# AMC_Connector.net
KiCad netlist of a schematic drawn in Altium Designer
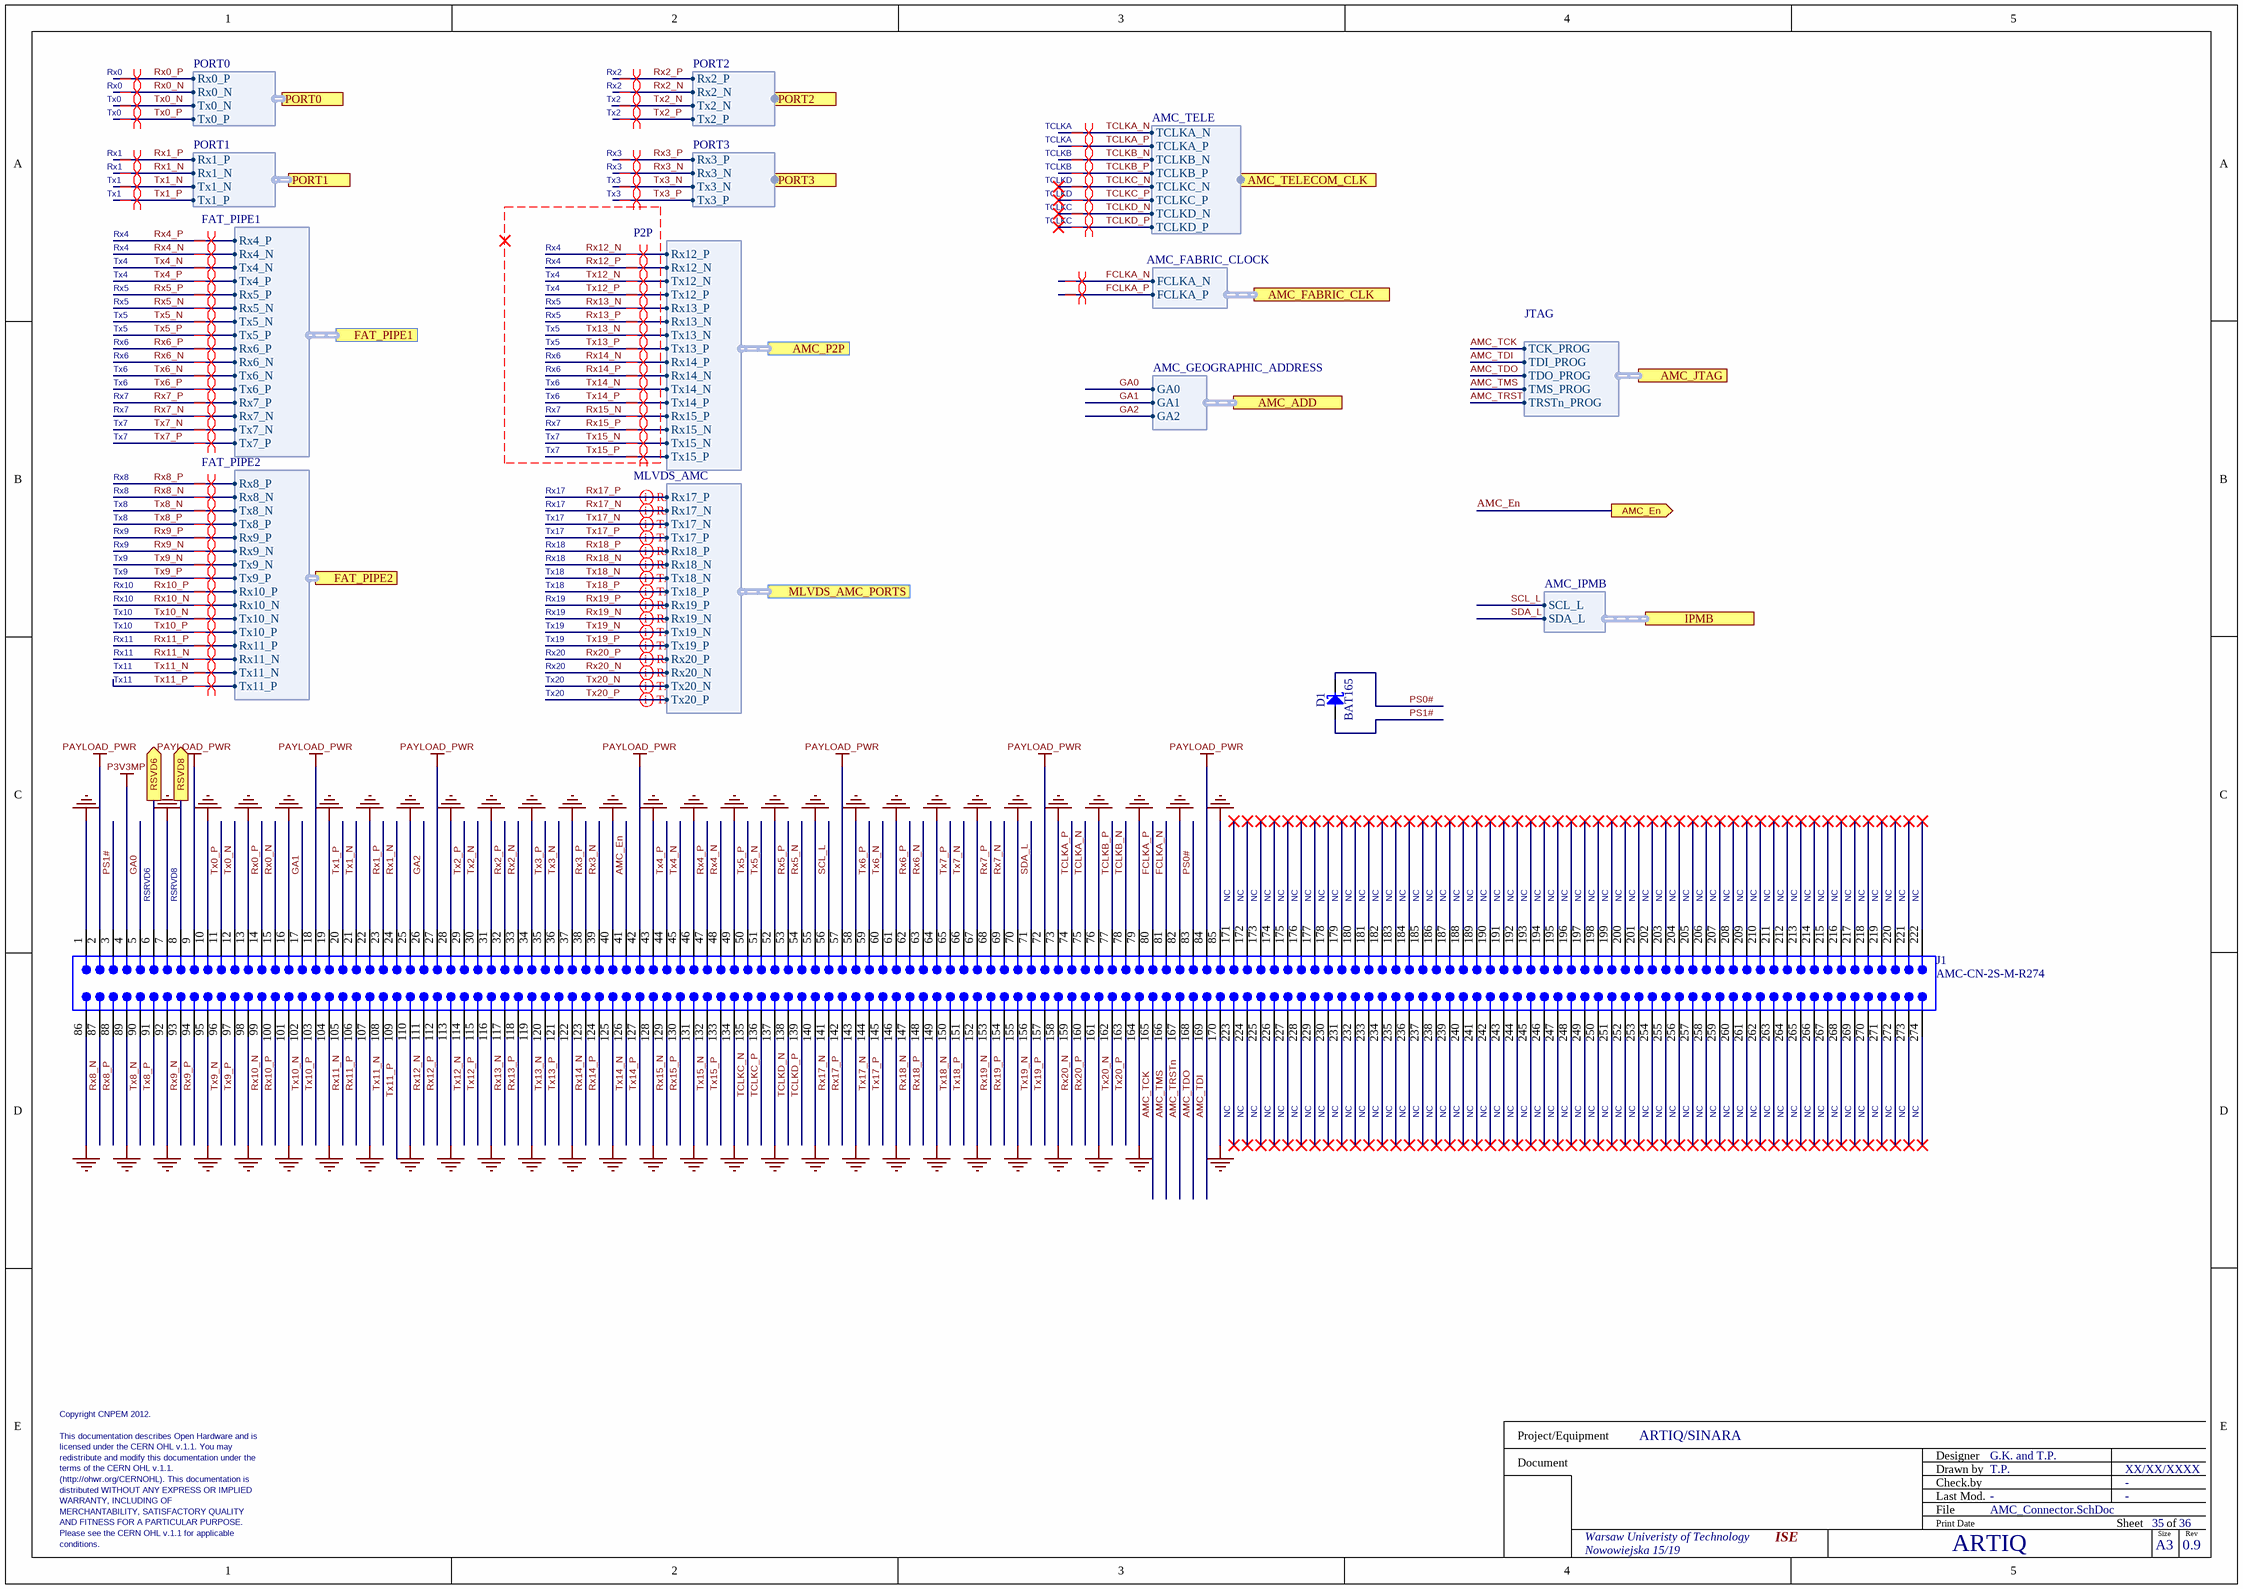
[diagram p0: AMC_Connector.SchDoc]

(export (version "E")
  (design (tool "Eeschema 10.0.6"))
  (components
    (comp (ref "D1")
      (value "BAT165")
      (footprint "SOD2512X110N")
      (description "Schottky Diode")
      (fields
        (field (name "MANUFACTURER") "INFINEON")
        (field (name "VOLTAGE") "40V")
        (field (name "AUTHOR") "CERN DEM JLC")
      )
      (libsource (lib "ICs And Semiconductors") (part "Diode Schottky"))
    )
    (comp (ref "J1")
      (value "AMC-CN-2S-M-R274")
      (footprint "AMC-GF-2D-750-O274")
      (description "Golden finger, AMC, Dual, Opposite, Pitch 0.75mm, 170-Position")
      (fields (field (name "PUBLISHER") "Altium"))
      (libsource (lib "Altium Shanghai") (part "CMP-0001-00058-2"))
    )
  )
  (nets
    (net (code "14") (name "/AMC_En") (class "Default")
      (node (ref "J1") (pin "41") (pinfunction "41_41") (pintype "passive"))
    )
    (net (code "15") (name "/AMC_TCK") (class "Default")
      (node (ref "J1") (pin "165") (pinfunction "165_165") (pintype "passive"))
    )
    (net (code "16") (name "/AMC_TDI") (class "Default")
      (node (ref "J1") (pin "169") (pinfunction "169_169") (pintype "passive"))
    )
    (net (code "17") (name "/AMC_TDO") (class "Default")
      (node (ref "J1") (pin "168") (pinfunction "168_168") (pintype "passive"))
    )
    (net (code "18") (name "/AMC_TMS") (class "Default")
      (node (ref "J1") (pin "166") (pinfunction "166_166") (pintype "passive"))
    )
    (net (code "19") (name "/AMC_TRSTn") (class "Default")
      (node (ref "J1") (pin "167") (pinfunction "167_167") (pintype "passive"))
    )
    (net (code "20") (name "/FCLKA_N") (class "Default")
      (node (ref "J1") (pin "81") (pinfunction "81_81") (pintype "passive"))
    )
    (net (code "21") (name "/FCLKA_P") (class "Default")
      (node (ref "J1") (pin "80") (pinfunction "80_80") (pintype "passive"))
    )
    (net (code "22") (name "/GA0") (class "Default")
      (node (ref "J1") (pin "5") (pinfunction "5_5") (pintype "passive"))
    )
    (net (code "23") (name "/GA1") (class "Default")
      (node (ref "J1") (pin "17") (pinfunction "17_17") (pintype "passive"))
    )
    (net (code "24") (name "/GA2") (class "Default")
      (node (ref "J1") (pin "26") (pinfunction "26_26") (pintype "passive"))
    )
    (net (code "25") (name "/PS0#") (class "Default")
      (node (ref "D1") (pin "1") (pinfunction "C_1") (pintype "passive"))
      (node (ref "J1") (pin "83") (pinfunction "83_83") (pintype "passive"))
    )
    (net (code "26") (name "/PS1#") (class "Default")
      (node (ref "D1") (pin "2") (pinfunction "A_2") (pintype "passive"))
      (node (ref "J1") (pin "3") (pinfunction "3_3") (pintype "passive"))
    )
    (net (code "27") (name "/RSVD6") (class "Default")
      (node (ref "J1") (pin "6") (pinfunction "6_6") (pintype "passive"))
    )
    (net (code "28") (name "/RSVD8") (class "Default")
      (node (ref "J1") (pin "8") (pinfunction "8_8") (pintype "passive"))
    )
    (net (code "29") (name "/Rx0_N") (class "Default")
      (node (ref "J1") (pin "15") (pinfunction "15_15") (pintype "passive"))
    )
    (net (code "30") (name "/Rx0_P") (class "Default")
      (node (ref "J1") (pin "14") (pinfunction "14_14") (pintype "passive"))
    )
    (net (code "31") (name "/Rx1_N") (class "Default")
      (node (ref "J1") (pin "24") (pinfunction "24_24") (pintype "passive"))
    )
    (net (code "32") (name "/Rx1_P") (class "Default")
      (node (ref "J1") (pin "23") (pinfunction "23_23") (pintype "passive"))
    )
    (net (code "33") (name "/Rx2_N") (class "Default")
      (node (ref "J1") (pin "33") (pinfunction "33_33") (pintype "passive"))
    )
    (net (code "34") (name "/Rx2_P") (class "Default")
      (node (ref "J1") (pin "32") (pinfunction "32_32") (pintype "passive"))
    )
    (net (code "35") (name "/Rx3_N") (class "Default")
      (node (ref "J1") (pin "39") (pinfunction "39_39") (pintype "passive"))
    )
    (net (code "36") (name "/Rx3_P") (class "Default")
      (node (ref "J1") (pin "38") (pinfunction "38_38") (pintype "passive"))
    )
    (net (code "37") (name "/Rx4_N") (class "Default")
      (node (ref "J1") (pin "48") (pinfunction "48_48") (pintype "passive"))
    )
    (net (code "38") (name "/Rx4_P") (class "Default")
      (node (ref "J1") (pin "47") (pinfunction "47_47") (pintype "passive"))
    )
    (net (code "39") (name "/Rx5_N") (class "Default")
      (node (ref "J1") (pin "54") (pinfunction "54_54") (pintype "passive"))
    )
    (net (code "40") (name "/Rx5_P") (class "Default")
      (node (ref "J1") (pin "53") (pinfunction "53_53") (pintype "passive"))
    )
    (net (code "41") (name "/Rx6_N") (class "Default")
      (node (ref "J1") (pin "63") (pinfunction "63_63") (pintype "passive"))
    )
    (net (code "42") (name "/Rx6_P") (class "Default")
      (node (ref "J1") (pin "62") (pinfunction "62_62") (pintype "passive"))
    )
    (net (code "43") (name "/Rx7_N") (class "Default")
      (node (ref "J1") (pin "69") (pinfunction "69_69") (pintype "passive"))
    )
    (net (code "44") (name "/Rx7_P") (class "Default")
      (node (ref "J1") (pin "68") (pinfunction "68_68") (pintype "passive"))
    )
    (net (code "45") (name "/Rx8_N") (class "Default")
      (node (ref "J1") (pin "87") (pinfunction "87_87") (pintype "passive"))
    )
    (net (code "46") (name "/Rx8_P") (class "Default")
      (node (ref "J1") (pin "88") (pinfunction "88_88") (pintype "passive"))
    )
    (net (code "47") (name "/Rx9_N") (class "Default")
      (node (ref "J1") (pin "93") (pinfunction "93_93") (pintype "passive"))
    )
    (net (code "48") (name "/Rx9_P") (class "Default")
      (node (ref "J1") (pin "94") (pinfunction "94_94") (pintype "passive"))
    )
    (net (code "49") (name "/Rx10_N") (class "Default")
      (node (ref "J1") (pin "99") (pinfunction "99_99") (pintype "passive"))
    )
    (net (code "50") (name "/Rx10_P") (class "Default")
      (node (ref "J1") (pin "100") (pinfunction "100_100") (pintype "passive"))
    )
    (net (code "51") (name "/Rx11_N") (class "Default")
      (node (ref "J1") (pin "105") (pinfunction "105_105") (pintype "passive"))
    )
    (net (code "52") (name "/Rx11_P") (class "Default")
      (node (ref "J1") (pin "106") (pinfunction "106_106") (pintype "passive"))
    )
    (net (code "53") (name "/Rx12_N") (class "Default")
      (node (ref "J1") (pin "111") (pinfunction "111_111") (pintype "passive"))
    )
    (net (code "54") (name "/Rx12_P") (class "Default")
      (node (ref "J1") (pin "112") (pinfunction "112_112") (pintype "passive"))
    )
    (net (code "55") (name "/Rx13_N") (class "Default")
      (node (ref "J1") (pin "117") (pinfunction "117_117") (pintype "passive"))
    )
    (net (code "56") (name "/Rx13_P") (class "Default")
      (node (ref "J1") (pin "118") (pinfunction "118_118") (pintype "passive"))
    )
    (net (code "57") (name "/Rx14_N") (class "Default")
      (node (ref "J1") (pin "123") (pinfunction "123_123") (pintype "passive"))
    )
    (net (code "58") (name "/Rx14_P") (class "Default")
      (node (ref "J1") (pin "124") (pinfunction "124_124") (pintype "passive"))
    )
    (net (code "59") (name "/Rx15_N") (class "Default")
      (node (ref "J1") (pin "129") (pinfunction "129_129") (pintype "passive"))
    )
    (net (code "60") (name "/Rx15_P") (class "Default")
      (node (ref "J1") (pin "130") (pinfunction "130_130") (pintype "passive"))
    )
    (net (code "61") (name "/Rx17_N") (class "Default")
      (node (ref "J1") (pin "141") (pinfunction "141_141") (pintype "passive"))
    )
    (net (code "62") (name "/Rx17_P") (class "Default")
      (node (ref "J1") (pin "142") (pinfunction "142_142") (pintype "passive"))
    )
    (net (code "63") (name "/Rx18_N") (class "Default")
      (node (ref "J1") (pin "147") (pinfunction "147_147") (pintype "passive"))
    )
    (net (code "64") (name "/Rx18_P") (class "Default")
      (node (ref "J1") (pin "148") (pinfunction "148_148") (pintype "passive"))
    )
    (net (code "65") (name "/Rx19_N") (class "Default")
      (node (ref "J1") (pin "153") (pinfunction "153_153") (pintype "passive"))
    )
    (net (code "66") (name "/Rx19_P") (class "Default")
      (node (ref "J1") (pin "154") (pinfunction "154_154") (pintype "passive"))
    )
    (net (code "67") (name "/Rx20_N") (class "Default")
      (node (ref "J1") (pin "159") (pinfunction "159_159") (pintype "passive"))
    )
    (net (code "68") (name "/Rx20_P") (class "Default")
      (node (ref "J1") (pin "160") (pinfunction "160_160") (pintype "passive"))
    )
    (net (code "69") (name "/SCL_L") (class "Default")
      (node (ref "J1") (pin "56") (pinfunction "56_56") (pintype "passive"))
    )
    (net (code "70") (name "/SDA_L") (class "Default")
      (node (ref "J1") (pin "71") (pinfunction "71_71") (pintype "passive"))
    )
    (net (code "71") (name "/TCLKA_N") (class "Default")
      (node (ref "J1") (pin "75") (pinfunction "75_75") (pintype "passive"))
    )
    (net (code "72") (name "/TCLKA_P") (class "Default")
      (node (ref "J1") (pin "74") (pinfunction "74_74") (pintype "passive"))
    )
    (net (code "73") (name "/TCLKB_N") (class "Default")
      (node (ref "J1") (pin "78") (pinfunction "78_78") (pintype "passive"))
    )
    (net (code "74") (name "/TCLKB_P") (class "Default")
      (node (ref "J1") (pin "77") (pinfunction "77_77") (pintype "passive"))
    )
    (net (code "75") (name "/TCLKC_N") (class "Default")
      (node (ref "J1") (pin "135") (pinfunction "135_135") (pintype "passive"))
    )
    (net (code "76") (name "/TCLKC_P") (class "Default")
      (node (ref "J1") (pin "136") (pinfunction "136_136") (pintype "passive"))
    )
    (net (code "77") (name "/TCLKD_N") (class "Default")
      (node (ref "J1") (pin "138") (pinfunction "138_138") (pintype "passive"))
    )
    (net (code "78") (name "/TCLKD_P") (class "Default")
      (node (ref "J1") (pin "139") (pinfunction "139_139") (pintype "passive"))
    )
    (net (code "79") (name "/Tx0_N") (class "Default")
      (node (ref "J1") (pin "12") (pinfunction "12_12") (pintype "passive"))
    )
    (net (code "80") (name "/Tx0_P") (class "Default")
      (node (ref "J1") (pin "11") (pinfunction "11_11") (pintype "passive"))
    )
    (net (code "81") (name "/Tx1_N") (class "Default")
      (node (ref "J1") (pin "21") (pinfunction "21_21") (pintype "passive"))
    )
    (net (code "82") (name "/Tx1_P") (class "Default")
      (node (ref "J1") (pin "20") (pinfunction "20_20") (pintype "passive"))
    )
    (net (code "83") (name "/Tx2_N") (class "Default")
      (node (ref "J1") (pin "30") (pinfunction "30_30") (pintype "passive"))
    )
    (net (code "84") (name "/Tx2_P") (class "Default")
      (node (ref "J1") (pin "29") (pinfunction "29_29") (pintype "passive"))
    )
    (net (code "85") (name "/Tx3_N") (class "Default")
      (node (ref "J1") (pin "36") (pinfunction "36_36") (pintype "passive"))
    )
    (net (code "86") (name "/Tx3_P") (class "Default")
      (node (ref "J1") (pin "35") (pinfunction "35_35") (pintype "passive"))
    )
    (net (code "87") (name "/Tx4_N") (class "Default")
      (node (ref "J1") (pin "45") (pinfunction "45_45") (pintype "passive"))
    )
    (net (code "88") (name "/Tx4_P") (class "Default")
      (node (ref "J1") (pin "44") (pinfunction "44_44") (pintype "passive"))
    )
    (net (code "89") (name "/Tx5_N") (class "Default")
      (node (ref "J1") (pin "51") (pinfunction "51_51") (pintype "passive"))
    )
    (net (code "90") (name "/Tx5_P") (class "Default")
      (node (ref "J1") (pin "50") (pinfunction "50_50") (pintype "passive"))
    )
    (net (code "91") (name "/Tx6_N") (class "Default")
      (node (ref "J1") (pin "60") (pinfunction "60_60") (pintype "passive"))
    )
    (net (code "92") (name "/Tx6_P") (class "Default")
      (node (ref "J1") (pin "59") (pinfunction "59_59") (pintype "passive"))
    )
    (net (code "93") (name "/Tx7_N") (class "Default")
      (node (ref "J1") (pin "66") (pinfunction "66_66") (pintype "passive"))
    )
    (net (code "94") (name "/Tx7_P") (class "Default")
      (node (ref "J1") (pin "65") (pinfunction "65_65") (pintype "passive"))
    )
    (net (code "95") (name "/Tx8_N") (class "Default")
      (node (ref "J1") (pin "90") (pinfunction "90_90") (pintype "passive"))
    )
    (net (code "96") (name "/Tx8_P") (class "Default")
      (node (ref "J1") (pin "91") (pinfunction "91_91") (pintype "passive"))
    )
    (net (code "97") (name "/Tx9_N") (class "Default")
      (node (ref "J1") (pin "96") (pinfunction "96_96") (pintype "passive"))
    )
    (net (code "98") (name "/Tx9_P") (class "Default")
      (node (ref "J1") (pin "97") (pinfunction "97_97") (pintype "passive"))
    )
    (net (code "99") (name "/Tx10_N") (class "Default")
      (node (ref "J1") (pin "102") (pinfunction "102_102") (pintype "passive"))
    )
    (net (code "100") (name "/Tx10_P") (class "Default")
      (node (ref "J1") (pin "103") (pinfunction "103_103") (pintype "passive"))
    )
    (net (code "101") (name "/Tx11_N") (class "Default")
      (node (ref "J1") (pin "108") (pinfunction "108_108") (pintype "passive"))
    )
    (net (code "102") (name "/Tx11_P") (class "Default")
      (node (ref "J1") (pin "109") (pinfunction "109_109") (pintype "passive"))
    )
    (net (code "103") (name "/Tx12_N") (class "Default")
      (node (ref "J1") (pin "114") (pinfunction "114_114") (pintype "passive"))
    )
    (net (code "104") (name "/Tx12_P") (class "Default")
      (node (ref "J1") (pin "115") (pinfunction "115_115") (pintype "passive"))
    )
    (net (code "105") (name "/Tx13_N") (class "Default")
      (node (ref "J1") (pin "120") (pinfunction "120_120") (pintype "passive"))
    )
    (net (code "106") (name "/Tx13_P") (class "Default")
      (node (ref "J1") (pin "121") (pinfunction "121_121") (pintype "passive"))
    )
    (net (code "107") (name "/Tx14_N") (class "Default")
      (node (ref "J1") (pin "126") (pinfunction "126_126") (pintype "passive"))
    )
    (net (code "108") (name "/Tx14_P") (class "Default")
      (node (ref "J1") (pin "127") (pinfunction "127_127") (pintype "passive"))
    )
    (net (code "109") (name "/Tx15_N") (class "Default")
      (node (ref "J1") (pin "132") (pinfunction "132_132") (pintype "passive"))
    )
    (net (code "110") (name "/Tx15_P") (class "Default")
      (node (ref "J1") (pin "133") (pinfunction "133_133") (pintype "passive"))
    )
    (net (code "111") (name "/Tx17_N") (class "Default")
      (node (ref "J1") (pin "144") (pinfunction "144_144") (pintype "passive"))
    )
    (net (code "112") (name "/Tx17_P") (class "Default")
      (node (ref "J1") (pin "145") (pinfunction "145_145") (pintype "passive"))
    )
    (net (code "113") (name "/Tx18_N") (class "Default")
      (node (ref "J1") (pin "150") (pinfunction "150_150") (pintype "passive"))
    )
    (net (code "114") (name "/Tx18_P") (class "Default")
      (node (ref "J1") (pin "151") (pinfunction "151_151") (pintype "passive"))
    )
    (net (code "115") (name "/Tx19_N") (class "Default")
      (node (ref "J1") (pin "156") (pinfunction "156_156") (pintype "passive"))
    )
    (net (code "116") (name "/Tx19_P") (class "Default")
      (node (ref "J1") (pin "157") (pinfunction "157_157") (pintype "passive"))
    )
    (net (code "117") (name "/Tx20_N") (class "Default")
      (node (ref "J1") (pin "162") (pinfunction "162_162") (pintype "passive"))
    )
    (net (code "118") (name "/Tx20_P") (class "Default")
      (node (ref "J1") (pin "163") (pinfunction "163_163") (pintype "passive"))
    )
    (net (code "132") (name "GND") (class "Default")
      (node (ref "J1") (pin "1") (pinfunction "1_1") (pintype "passive"))
      (node (ref "J1") (pin "10") (pinfunction "10_10") (pintype "passive"))
      (node (ref "J1") (pin "101") (pinfunction "101_101") (pintype "passive"))
      (node (ref "J1") (pin "104") (pinfunction "104_104") (pintype "passive"))
      (node (ref "J1") (pin "107") (pinfunction "107_107") (pintype "passive"))
      (node (ref "J1") (pin "110") (pinfunction "110_110") (pintype "passive"))
      (node (ref "J1") (pin "113") (pinfunction "113_113") (pintype "passive"))
      (node (ref "J1") (pin "116") (pinfunction "116_116") (pintype "passive"))
      (node (ref "J1") (pin "119") (pinfunction "119_119") (pintype "passive"))
      (node (ref "J1") (pin "122") (pinfunction "122_122") (pintype "passive"))
      (node (ref "J1") (pin "125") (pinfunction "125_125") (pintype "passive"))
      (node (ref "J1") (pin "128") (pinfunction "128_128") (pintype "passive"))
      (node (ref "J1") (pin "13") (pinfunction "13_13") (pintype "passive"))
      (node (ref "J1") (pin "131") (pinfunction "131_131") (pintype "passive"))
      (node (ref "J1") (pin "134") (pinfunction "134_134") (pintype "passive"))
      (node (ref "J1") (pin "137") (pinfunction "137_137") (pintype "passive"))
      (node (ref "J1") (pin "140") (pinfunction "140_140") (pintype "passive"))
      (node (ref "J1") (pin "143") (pinfunction "143_143") (pintype "passive"))
      (node (ref "J1") (pin "146") (pinfunction "146_146") (pintype "passive"))
      (node (ref "J1") (pin "149") (pinfunction "149_149") (pintype "passive"))
      (node (ref "J1") (pin "152") (pinfunction "152_152") (pintype "passive"))
      (node (ref "J1") (pin "155") (pinfunction "155_155") (pintype "passive"))
      (node (ref "J1") (pin "158") (pinfunction "158_158") (pintype "passive"))
      (node (ref "J1") (pin "16") (pinfunction "16_16") (pintype "passive"))
      (node (ref "J1") (pin "161") (pinfunction "161_161") (pintype "passive"))
      (node (ref "J1") (pin "164") (pinfunction "164_164") (pintype "passive"))
      (node (ref "J1") (pin "170") (pinfunction "170_170") (pintype "passive"))
      (node (ref "J1") (pin "19") (pinfunction "19_19") (pintype "passive"))
      (node (ref "J1") (pin "22") (pinfunction "22_22") (pintype "passive"))
      (node (ref "J1") (pin "25") (pinfunction "25_25") (pintype "passive"))
      (node (ref "J1") (pin "28") (pinfunction "28_28") (pintype "passive"))
      (node (ref "J1") (pin "31") (pinfunction "31_31") (pintype "passive"))
      (node (ref "J1") (pin "34") (pinfunction "34_34") (pintype "passive"))
      (node (ref "J1") (pin "37") (pinfunction "37_37") (pintype "passive"))
      (node (ref "J1") (pin "40") (pinfunction "40_40") (pintype "passive"))
      (node (ref "J1") (pin "43") (pinfunction "43_43") (pintype "passive"))
      (node (ref "J1") (pin "46") (pinfunction "46_46") (pintype "passive"))
      (node (ref "J1") (pin "49") (pinfunction "49_49") (pintype "passive"))
      (node (ref "J1") (pin "52") (pinfunction "52_52") (pintype "passive"))
      (node (ref "J1") (pin "55") (pinfunction "55_55") (pintype "passive"))
      (node (ref "J1") (pin "58") (pinfunction "58_58") (pintype "passive"))
      (node (ref "J1") (pin "61") (pinfunction "61_61") (pintype "passive"))
      (node (ref "J1") (pin "64") (pinfunction "64_64") (pintype "passive"))
      (node (ref "J1") (pin "67") (pinfunction "67_67") (pintype "passive"))
      (node (ref "J1") (pin "7") (pinfunction "7_7") (pintype "passive"))
      (node (ref "J1") (pin "70") (pinfunction "70_70") (pintype "passive"))
      (node (ref "J1") (pin "73") (pinfunction "73_73") (pintype "passive"))
      (node (ref "J1") (pin "76") (pinfunction "76_76") (pintype "passive"))
      (node (ref "J1") (pin "79") (pinfunction "79_79") (pintype "passive"))
      (node (ref "J1") (pin "82") (pinfunction "82_82") (pintype "passive"))
      (node (ref "J1") (pin "85") (pinfunction "85_85") (pintype "passive"))
      (node (ref "J1") (pin "86") (pinfunction "86_86") (pintype "passive"))
      (node (ref "J1") (pin "89") (pinfunction "89_89") (pintype "passive"))
      (node (ref "J1") (pin "92") (pinfunction "92_92") (pintype "passive"))
      (node (ref "J1") (pin "95") (pinfunction "95_95") (pintype "passive"))
      (node (ref "J1") (pin "98") (pinfunction "98_98") (pintype "passive"))
    )
    (net (code "133") (name "P3V3MP") (class "Default")
      (node (ref "J1") (pin "4") (pinfunction "4_4") (pintype "passive"))
    )
    (net (code "134") (name "PAYLOAD_PWR") (class "Default")
      (node (ref "J1") (pin "18") (pinfunction "18_18") (pintype "passive"))
      (node (ref "J1") (pin "2") (pinfunction "2_2") (pintype "passive"))
      (node (ref "J1") (pin "27") (pinfunction "27_27") (pintype "passive"))
      (node (ref "J1") (pin "42") (pinfunction "42_42") (pintype "passive"))
      (node (ref "J1") (pin "57") (pinfunction "57_57") (pintype "passive"))
      (node (ref "J1") (pin "72") (pinfunction "72_72") (pintype "passive"))
      (node (ref "J1") (pin "84") (pinfunction "84_84") (pintype "passive"))
      (node (ref "J1") (pin "9") (pinfunction "9_9") (pintype "passive"))
    )
    (net (code "135") (name "unconnected-(J1-Pad171)") (class "Default")
      (node (ref "J1") (pin "171") (pinfunction "171_171") (pintype "passive+no_connect"))
    )
    (net (code "136") (name "unconnected-(J1-Pad172)") (class "Default")
      (node (ref "J1") (pin "172") (pinfunction "172_172") (pintype "passive+no_connect"))
    )
    (net (code "137") (name "unconnected-(J1-Pad173)") (class "Default")
      (node (ref "J1") (pin "173") (pinfunction "173_173") (pintype "passive+no_connect"))
    )
    (net (code "138") (name "unconnected-(J1-Pad174)") (class "Default")
      (node (ref "J1") (pin "174") (pinfunction "174_174") (pintype "passive+no_connect"))
    )
    (net (code "139") (name "unconnected-(J1-Pad175)") (class "Default")
      (node (ref "J1") (pin "175") (pinfunction "175_175") (pintype "passive+no_connect"))
    )
    (net (code "140") (name "unconnected-(J1-Pad176)") (class "Default")
      (node (ref "J1") (pin "176") (pinfunction "176_176") (pintype "passive+no_connect"))
    )
    (net (code "141") (name "unconnected-(J1-Pad177)") (class "Default")
      (node (ref "J1") (pin "177") (pinfunction "177_177") (pintype "passive+no_connect"))
    )
    (net (code "142") (name "unconnected-(J1-Pad178)") (class "Default")
      (node (ref "J1") (pin "178") (pinfunction "178_178") (pintype "passive+no_connect"))
    )
    (net (code "143") (name "unconnected-(J1-Pad179)") (class "Default")
      (node (ref "J1") (pin "179") (pinfunction "179_179") (pintype "passive+no_connect"))
    )
    (net (code "144") (name "unconnected-(J1-Pad180)") (class "Default")
      (node (ref "J1") (pin "180") (pinfunction "180_180") (pintype "passive+no_connect"))
    )
    (net (code "145") (name "unconnected-(J1-Pad181)") (class "Default")
      (node (ref "J1") (pin "181") (pinfunction "181_181") (pintype "passive+no_connect"))
    )
    (net (code "146") (name "unconnected-(J1-Pad182)") (class "Default")
      (node (ref "J1") (pin "182") (pinfunction "182_182") (pintype "passive+no_connect"))
    )
    (net (code "147") (name "unconnected-(J1-Pad183)") (class "Default")
      (node (ref "J1") (pin "183") (pinfunction "183_183") (pintype "passive+no_connect"))
    )
    (net (code "148") (name "unconnected-(J1-Pad184)") (class "Default")
      (node (ref "J1") (pin "184") (pinfunction "184_184") (pintype "passive+no_connect"))
    )
    (net (code "149") (name "unconnected-(J1-Pad185)") (class "Default")
      (node (ref "J1") (pin "185") (pinfunction "185_185") (pintype "passive+no_connect"))
    )
    (net (code "150") (name "unconnected-(J1-Pad186)") (class "Default")
      (node (ref "J1") (pin "186") (pinfunction "186_186") (pintype "passive+no_connect"))
    )
    (net (code "151") (name "unconnected-(J1-Pad187)") (class "Default")
      (node (ref "J1") (pin "187") (pinfunction "187_187") (pintype "passive+no_connect"))
    )
    (net (code "152") (name "unconnected-(J1-Pad188)") (class "Default")
      (node (ref "J1") (pin "188") (pinfunction "188_188") (pintype "passive+no_connect"))
    )
    (net (code "153") (name "unconnected-(J1-Pad189)") (class "Default")
      (node (ref "J1") (pin "189") (pinfunction "189_189") (pintype "passive+no_connect"))
    )
    (net (code "154") (name "unconnected-(J1-Pad190)") (class "Default")
      (node (ref "J1") (pin "190") (pinfunction "190_190") (pintype "passive+no_connect"))
    )
    (net (code "155") (name "unconnected-(J1-Pad191)") (class "Default")
      (node (ref "J1") (pin "191") (pinfunction "191_191") (pintype "passive+no_connect"))
    )
    (net (code "156") (name "unconnected-(J1-Pad192)") (class "Default")
      (node (ref "J1") (pin "192") (pinfunction "192_192") (pintype "passive+no_connect"))
    )
    (net (code "157") (name "unconnected-(J1-Pad193)") (class "Default")
      (node (ref "J1") (pin "193") (pinfunction "193_193") (pintype "passive+no_connect"))
    )
    (net (code "158") (name "unconnected-(J1-Pad194)") (class "Default")
      (node (ref "J1") (pin "194") (pinfunction "194_194") (pintype "passive+no_connect"))
    )
    (net (code "159") (name "unconnected-(J1-Pad195)") (class "Default")
      (node (ref "J1") (pin "195") (pinfunction "195_195") (pintype "passive+no_connect"))
    )
    (net (code "160") (name "unconnected-(J1-Pad196)") (class "Default")
      (node (ref "J1") (pin "196") (pinfunction "196_196") (pintype "passive+no_connect"))
    )
    (net (code "161") (name "unconnected-(J1-Pad197)") (class "Default")
      (node (ref "J1") (pin "197") (pinfunction "197_197") (pintype "passive+no_connect"))
    )
    (net (code "162") (name "unconnected-(J1-Pad198)") (class "Default")
      (node (ref "J1") (pin "198") (pinfunction "198_198") (pintype "passive+no_connect"))
    )
    (net (code "163") (name "unconnected-(J1-Pad199)") (class "Default")
      (node (ref "J1") (pin "199") (pinfunction "199_199") (pintype "passive+no_connect"))
    )
    (net (code "164") (name "unconnected-(J1-Pad200)") (class "Default")
      (node (ref "J1") (pin "200") (pinfunction "200_200") (pintype "passive+no_connect"))
    )
    (net (code "165") (name "unconnected-(J1-Pad201)") (class "Default")
      (node (ref "J1") (pin "201") (pinfunction "201_201") (pintype "passive+no_connect"))
    )
    (net (code "166") (name "unconnected-(J1-Pad202)") (class "Default")
      (node (ref "J1") (pin "202") (pinfunction "202_202") (pintype "passive+no_connect"))
    )
    (net (code "167") (name "unconnected-(J1-Pad203)") (class "Default")
      (node (ref "J1") (pin "203") (pinfunction "203_203") (pintype "passive+no_connect"))
    )
    (net (code "168") (name "unconnected-(J1-Pad204)") (class "Default")
      (node (ref "J1") (pin "204") (pinfunction "204_204") (pintype "passive+no_connect"))
    )
    (net (code "169") (name "unconnected-(J1-Pad205)") (class "Default")
      (node (ref "J1") (pin "205") (pinfunction "205_205") (pintype "passive+no_connect"))
    )
    (net (code "170") (name "unconnected-(J1-Pad206)") (class "Default")
      (node (ref "J1") (pin "206") (pinfunction "206_206") (pintype "passive+no_connect"))
    )
    (net (code "171") (name "unconnected-(J1-Pad207)") (class "Default")
      (node (ref "J1") (pin "207") (pinfunction "207_207") (pintype "passive+no_connect"))
    )
    (net (code "172") (name "unconnected-(J1-Pad208)") (class "Default")
      (node (ref "J1") (pin "208") (pinfunction "208_208") (pintype "passive+no_connect"))
    )
    (net (code "173") (name "unconnected-(J1-Pad209)") (class "Default")
      (node (ref "J1") (pin "209") (pinfunction "209_209") (pintype "passive+no_connect"))
    )
    (net (code "174") (name "unconnected-(J1-Pad210)") (class "Default")
      (node (ref "J1") (pin "210") (pinfunction "210_210") (pintype "passive+no_connect"))
    )
    (net (code "175") (name "unconnected-(J1-Pad211)") (class "Default")
      (node (ref "J1") (pin "211") (pinfunction "211_211") (pintype "passive+no_connect"))
    )
    (net (code "176") (name "unconnected-(J1-Pad212)") (class "Default")
      (node (ref "J1") (pin "212") (pinfunction "212_212") (pintype "passive+no_connect"))
    )
    (net (code "177") (name "unconnected-(J1-Pad213)") (class "Default")
      (node (ref "J1") (pin "213") (pinfunction "213_213") (pintype "passive+no_connect"))
    )
    (net (code "178") (name "unconnected-(J1-Pad214)") (class "Default")
      (node (ref "J1") (pin "214") (pinfunction "214_214") (pintype "passive+no_connect"))
    )
    (net (code "179") (name "unconnected-(J1-Pad215)") (class "Default")
      (node (ref "J1") (pin "215") (pinfunction "215_215") (pintype "passive+no_connect"))
    )
    (net (code "180") (name "unconnected-(J1-Pad216)") (class "Default")
      (node (ref "J1") (pin "216") (pinfunction "216_216") (pintype "passive+no_connect"))
    )
    (net (code "181") (name "unconnected-(J1-Pad217)") (class "Default")
      (node (ref "J1") (pin "217") (pinfunction "217_217") (pintype "passive+no_connect"))
    )
    (net (code "182") (name "unconnected-(J1-Pad218)") (class "Default")
      (node (ref "J1") (pin "218") (pinfunction "218_218") (pintype "passive+no_connect"))
    )
    (net (code "183") (name "unconnected-(J1-Pad219)") (class "Default")
      (node (ref "J1") (pin "219") (pinfunction "219_219") (pintype "passive+no_connect"))
    )
    (net (code "184") (name "unconnected-(J1-Pad220)") (class "Default")
      (node (ref "J1") (pin "220") (pinfunction "220_220") (pintype "passive+no_connect"))
    )
    (net (code "185") (name "unconnected-(J1-Pad221)") (class "Default")
      (node (ref "J1") (pin "221") (pinfunction "221_221") (pintype "passive+no_connect"))
    )
    (net (code "186") (name "unconnected-(J1-Pad222)") (class "Default")
      (node (ref "J1") (pin "222") (pinfunction "222_222") (pintype "passive+no_connect"))
    )
    (net (code "187") (name "unconnected-(J1-Pad223)") (class "Default")
      (node (ref "J1") (pin "223") (pinfunction "223_223") (pintype "passive+no_connect"))
    )
    (net (code "188") (name "unconnected-(J1-Pad224)") (class "Default")
      (node (ref "J1") (pin "224") (pinfunction "224_224") (pintype "passive+no_connect"))
    )
    (net (code "189") (name "unconnected-(J1-Pad225)") (class "Default")
      (node (ref "J1") (pin "225") (pinfunction "225_225") (pintype "passive+no_connect"))
    )
    (net (code "190") (name "unconnected-(J1-Pad226)") (class "Default")
      (node (ref "J1") (pin "226") (pinfunction "226_226") (pintype "passive+no_connect"))
    )
    (net (code "191") (name "unconnected-(J1-Pad227)") (class "Default")
      (node (ref "J1") (pin "227") (pinfunction "227_227") (pintype "passive+no_connect"))
    )
    (net (code "192") (name "unconnected-(J1-Pad228)") (class "Default")
      (node (ref "J1") (pin "228") (pinfunction "228_228") (pintype "passive+no_connect"))
    )
    (net (code "193") (name "unconnected-(J1-Pad229)") (class "Default")
      (node (ref "J1") (pin "229") (pinfunction "229_229") (pintype "passive+no_connect"))
    )
    (net (code "194") (name "unconnected-(J1-Pad230)") (class "Default")
      (node (ref "J1") (pin "230") (pinfunction "230_230") (pintype "passive+no_connect"))
    )
    (net (code "195") (name "unconnected-(J1-Pad231)") (class "Default")
      (node (ref "J1") (pin "231") (pinfunction "231_231") (pintype "passive+no_connect"))
    )
    (net (code "196") (name "unconnected-(J1-Pad232)") (class "Default")
      (node (ref "J1") (pin "232") (pinfunction "232_232") (pintype "passive+no_connect"))
    )
    (net (code "197") (name "unconnected-(J1-Pad233)") (class "Default")
      (node (ref "J1") (pin "233") (pinfunction "233_233") (pintype "passive+no_connect"))
    )
    (net (code "198") (name "unconnected-(J1-Pad234)") (class "Default")
      (node (ref "J1") (pin "234") (pinfunction "234_234") (pintype "passive+no_connect"))
    )
    (net (code "199") (name "unconnected-(J1-Pad235)") (class "Default")
      (node (ref "J1") (pin "235") (pinfunction "235_235") (pintype "passive+no_connect"))
    )
    (net (code "200") (name "unconnected-(J1-Pad236)") (class "Default")
      (node (ref "J1") (pin "236") (pinfunction "236_236") (pintype "passive+no_connect"))
    )
    (net (code "201") (name "unconnected-(J1-Pad237)") (class "Default")
      (node (ref "J1") (pin "237") (pinfunction "237_237") (pintype "passive+no_connect"))
    )
    (net (code "202") (name "unconnected-(J1-Pad238)") (class "Default")
      (node (ref "J1") (pin "238") (pinfunction "238_238") (pintype "passive+no_connect"))
    )
    (net (code "203") (name "unconnected-(J1-Pad239)") (class "Default")
      (node (ref "J1") (pin "239") (pinfunction "239_239") (pintype "passive+no_connect"))
    )
    (net (code "204") (name "unconnected-(J1-Pad240)") (class "Default")
      (node (ref "J1") (pin "240") (pinfunction "240_240") (pintype "passive+no_connect"))
    )
    (net (code "205") (name "unconnected-(J1-Pad241)") (class "Default")
      (node (ref "J1") (pin "241") (pinfunction "241_241") (pintype "passive+no_connect"))
    )
    (net (code "206") (name "unconnected-(J1-Pad242)") (class "Default")
      (node (ref "J1") (pin "242") (pinfunction "242_242") (pintype "passive+no_connect"))
    )
    (net (code "207") (name "unconnected-(J1-Pad243)") (class "Default")
      (node (ref "J1") (pin "243") (pinfunction "243_243") (pintype "passive+no_connect"))
    )
    (net (code "208") (name "unconnected-(J1-Pad244)") (class "Default")
      (node (ref "J1") (pin "244") (pinfunction "244_244") (pintype "passive+no_connect"))
    )
    (net (code "209") (name "unconnected-(J1-Pad245)") (class "Default")
      (node (ref "J1") (pin "245") (pinfunction "245_245") (pintype "passive+no_connect"))
    )
    (net (code "210") (name "unconnected-(J1-Pad246)") (class "Default")
      (node (ref "J1") (pin "246") (pinfunction "246_246") (pintype "passive+no_connect"))
    )
    (net (code "211") (name "unconnected-(J1-Pad247)") (class "Default")
      (node (ref "J1") (pin "247") (pinfunction "247_247") (pintype "passive+no_connect"))
    )
    (net (code "212") (name "unconnected-(J1-Pad248)") (class "Default")
      (node (ref "J1") (pin "248") (pinfunction "248_248") (pintype "passive+no_connect"))
    )
    (net (code "213") (name "unconnected-(J1-Pad249)") (class "Default")
      (node (ref "J1") (pin "249") (pinfunction "249_249") (pintype "passive+no_connect"))
    )
    (net (code "214") (name "unconnected-(J1-Pad250)") (class "Default")
      (node (ref "J1") (pin "250") (pinfunction "250_250") (pintype "passive+no_connect"))
    )
    (net (code "215") (name "unconnected-(J1-Pad251)") (class "Default")
      (node (ref "J1") (pin "251") (pinfunction "251_251") (pintype "passive+no_connect"))
    )
    (net (code "216") (name "unconnected-(J1-Pad252)") (class "Default")
      (node (ref "J1") (pin "252") (pinfunction "252_252") (pintype "passive+no_connect"))
    )
    (net (code "217") (name "unconnected-(J1-Pad253)") (class "Default")
      (node (ref "J1") (pin "253") (pinfunction "253_253") (pintype "passive+no_connect"))
    )
    (net (code "218") (name "unconnected-(J1-Pad254)") (class "Default")
      (node (ref "J1") (pin "254") (pinfunction "254_254") (pintype "passive+no_connect"))
    )
    (net (code "219") (name "unconnected-(J1-Pad255)") (class "Default")
      (node (ref "J1") (pin "255") (pinfunction "255_255") (pintype "passive+no_connect"))
    )
    (net (code "220") (name "unconnected-(J1-Pad256)") (class "Default")
      (node (ref "J1") (pin "256") (pinfunction "256_256") (pintype "passive+no_connect"))
    )
    (net (code "221") (name "unconnected-(J1-Pad257)") (class "Default")
      (node (ref "J1") (pin "257") (pinfunction "257_257") (pintype "passive+no_connect"))
    )
    (net (code "222") (name "unconnected-(J1-Pad258)") (class "Default")
      (node (ref "J1") (pin "258") (pinfunction "258_258") (pintype "passive+no_connect"))
    )
    (net (code "223") (name "unconnected-(J1-Pad259)") (class "Default")
      (node (ref "J1") (pin "259") (pinfunction "259_259") (pintype "passive+no_connect"))
    )
    (net (code "224") (name "unconnected-(J1-Pad260)") (class "Default")
      (node (ref "J1") (pin "260") (pinfunction "260_260") (pintype "passive+no_connect"))
    )
    (net (code "225") (name "unconnected-(J1-Pad261)") (class "Default")
      (node (ref "J1") (pin "261") (pinfunction "261_261") (pintype "passive+no_connect"))
    )
    (net (code "226") (name "unconnected-(J1-Pad262)") (class "Default")
      (node (ref "J1") (pin "262") (pinfunction "262_262") (pintype "passive+no_connect"))
    )
    (net (code "227") (name "unconnected-(J1-Pad263)") (class "Default")
      (node (ref "J1") (pin "263") (pinfunction "263_263") (pintype "passive+no_connect"))
    )
    (net (code "228") (name "unconnected-(J1-Pad264)") (class "Default")
      (node (ref "J1") (pin "264") (pinfunction "264_264") (pintype "passive+no_connect"))
    )
    (net (code "229") (name "unconnected-(J1-Pad265)") (class "Default")
      (node (ref "J1") (pin "265") (pinfunction "265_265") (pintype "passive+no_connect"))
    )
    (net (code "230") (name "unconnected-(J1-Pad266)") (class "Default")
      (node (ref "J1") (pin "266") (pinfunction "266_266") (pintype "passive+no_connect"))
    )
    (net (code "231") (name "unconnected-(J1-Pad267)") (class "Default")
      (node (ref "J1") (pin "267") (pinfunction "267_267") (pintype "passive+no_connect"))
    )
    (net (code "232") (name "unconnected-(J1-Pad268)") (class "Default")
      (node (ref "J1") (pin "268") (pinfunction "268_268") (pintype "passive+no_connect"))
    )
    (net (code "233") (name "unconnected-(J1-Pad269)") (class "Default")
      (node (ref "J1") (pin "269") (pinfunction "269_269") (pintype "passive+no_connect"))
    )
    (net (code "234") (name "unconnected-(J1-Pad270)") (class "Default")
      (node (ref "J1") (pin "270") (pinfunction "270_270") (pintype "passive+no_connect"))
    )
    (net (code "235") (name "unconnected-(J1-Pad271)") (class "Default")
      (node (ref "J1") (pin "271") (pinfunction "271_271") (pintype "passive+no_connect"))
    )
    (net (code "236") (name "unconnected-(J1-Pad272)") (class "Default")
      (node (ref "J1") (pin "272") (pinfunction "272_272") (pintype "passive+no_connect"))
    )
    (net (code "237") (name "unconnected-(J1-Pad273)") (class "Default")
      (node (ref "J1") (pin "273") (pinfunction "273_273") (pintype "passive+no_connect"))
    )
    (net (code "238") (name "unconnected-(J1-Pad274)") (class "Default")
      (node (ref "J1") (pin "274") (pinfunction "274_274") (pintype "passive+no_connect"))
    )
  )
)
